# Breakoutboard.net
KiCad netlist of a schematic drawn in Altium Designer
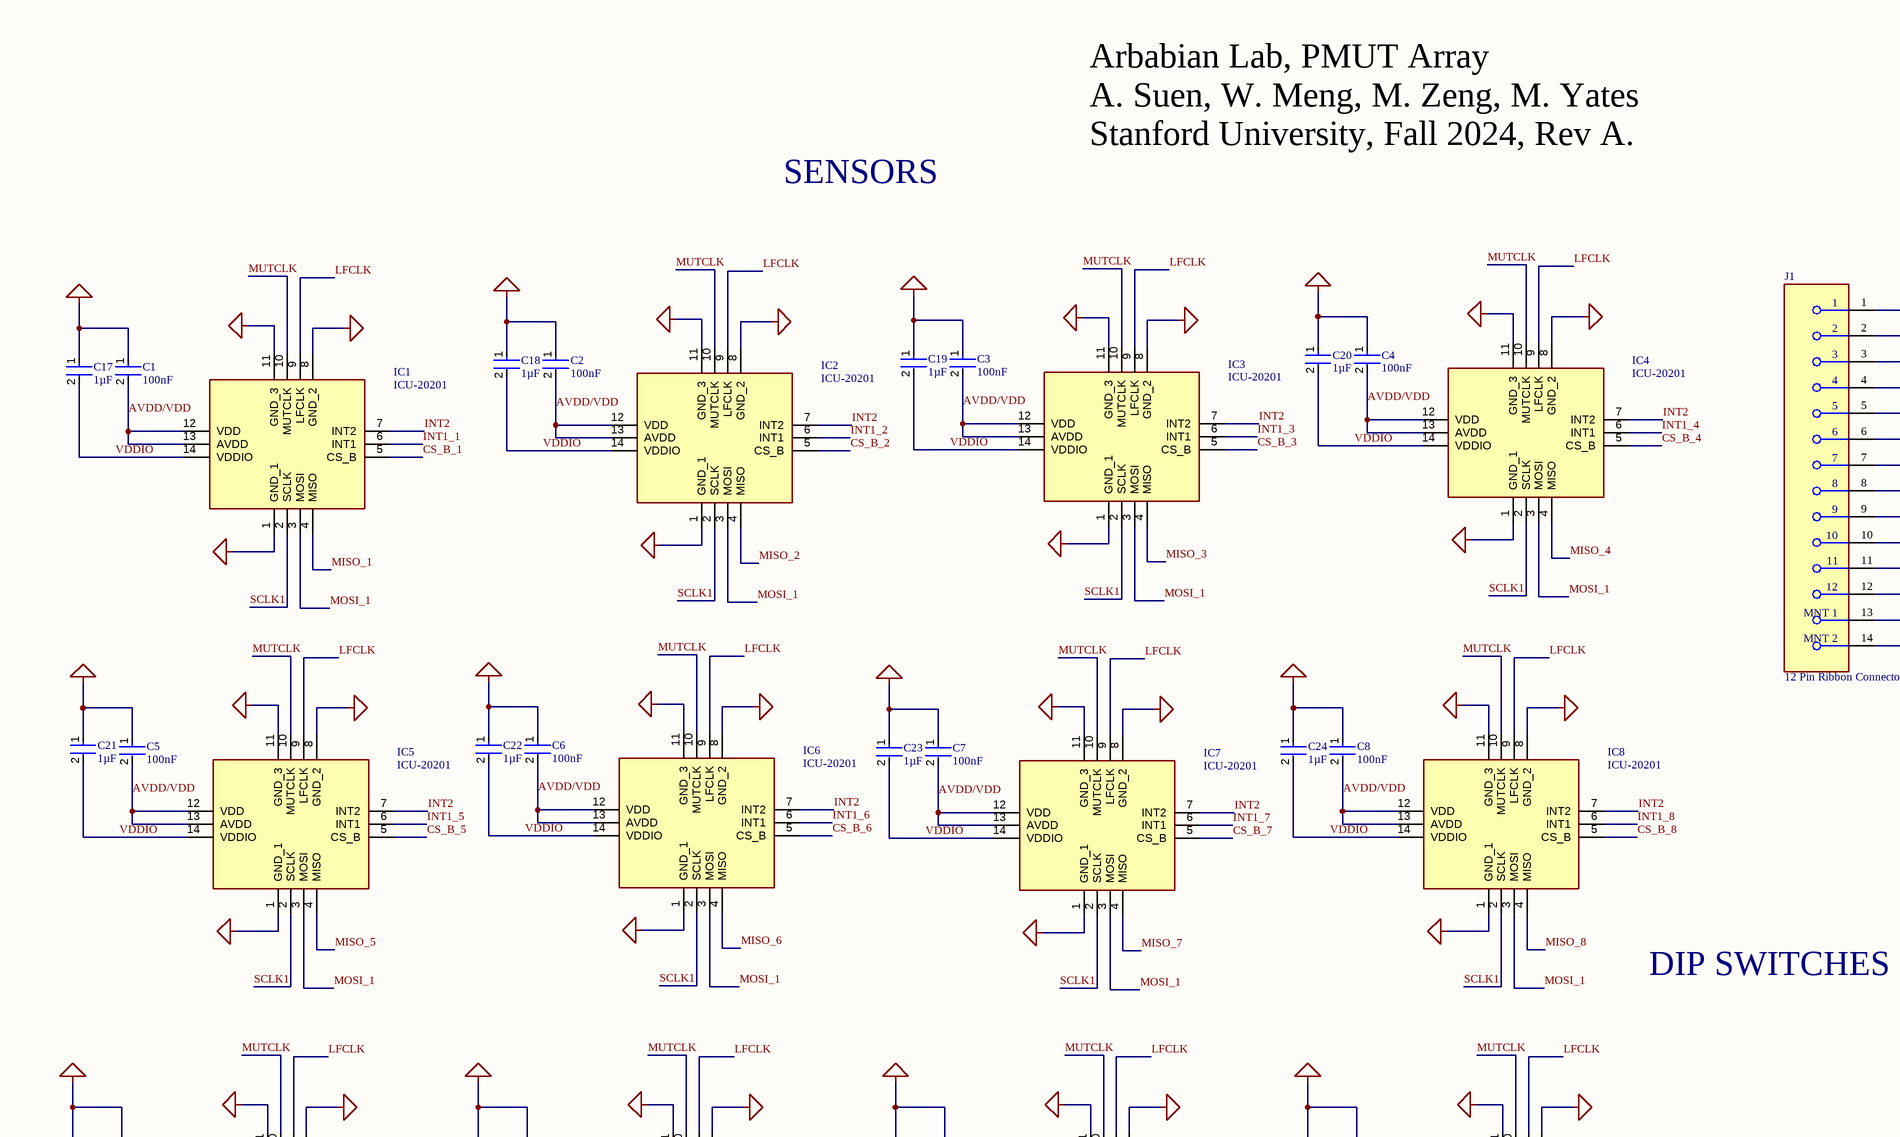
[diagram p0: Breakoutboard.SchDoc, top left]
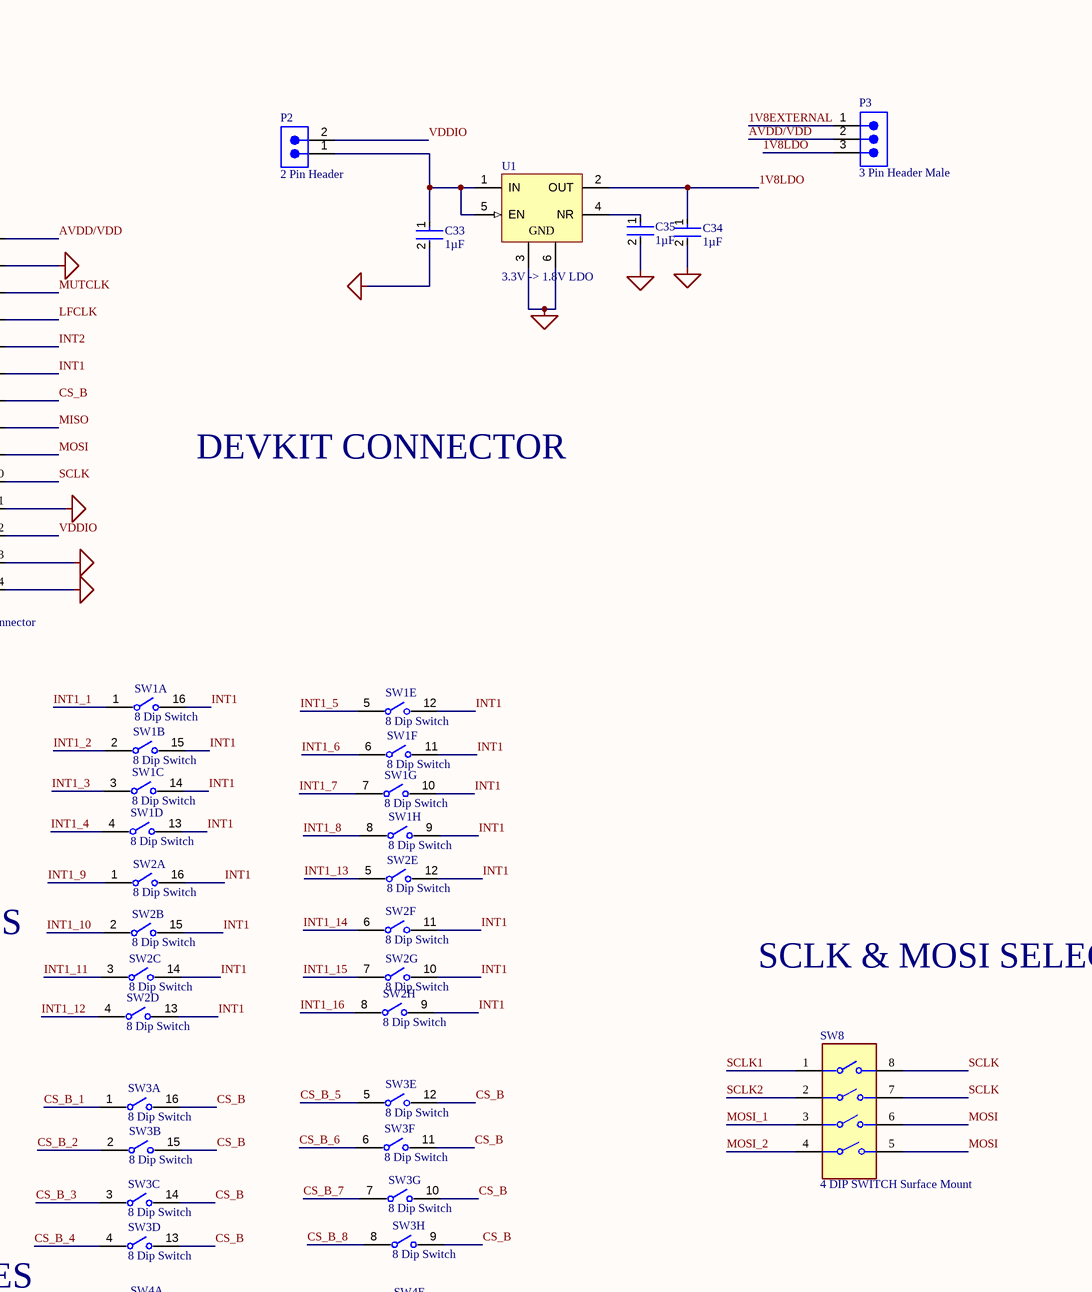
[diagram p1: Breakoutboard.SchDoc, top right]
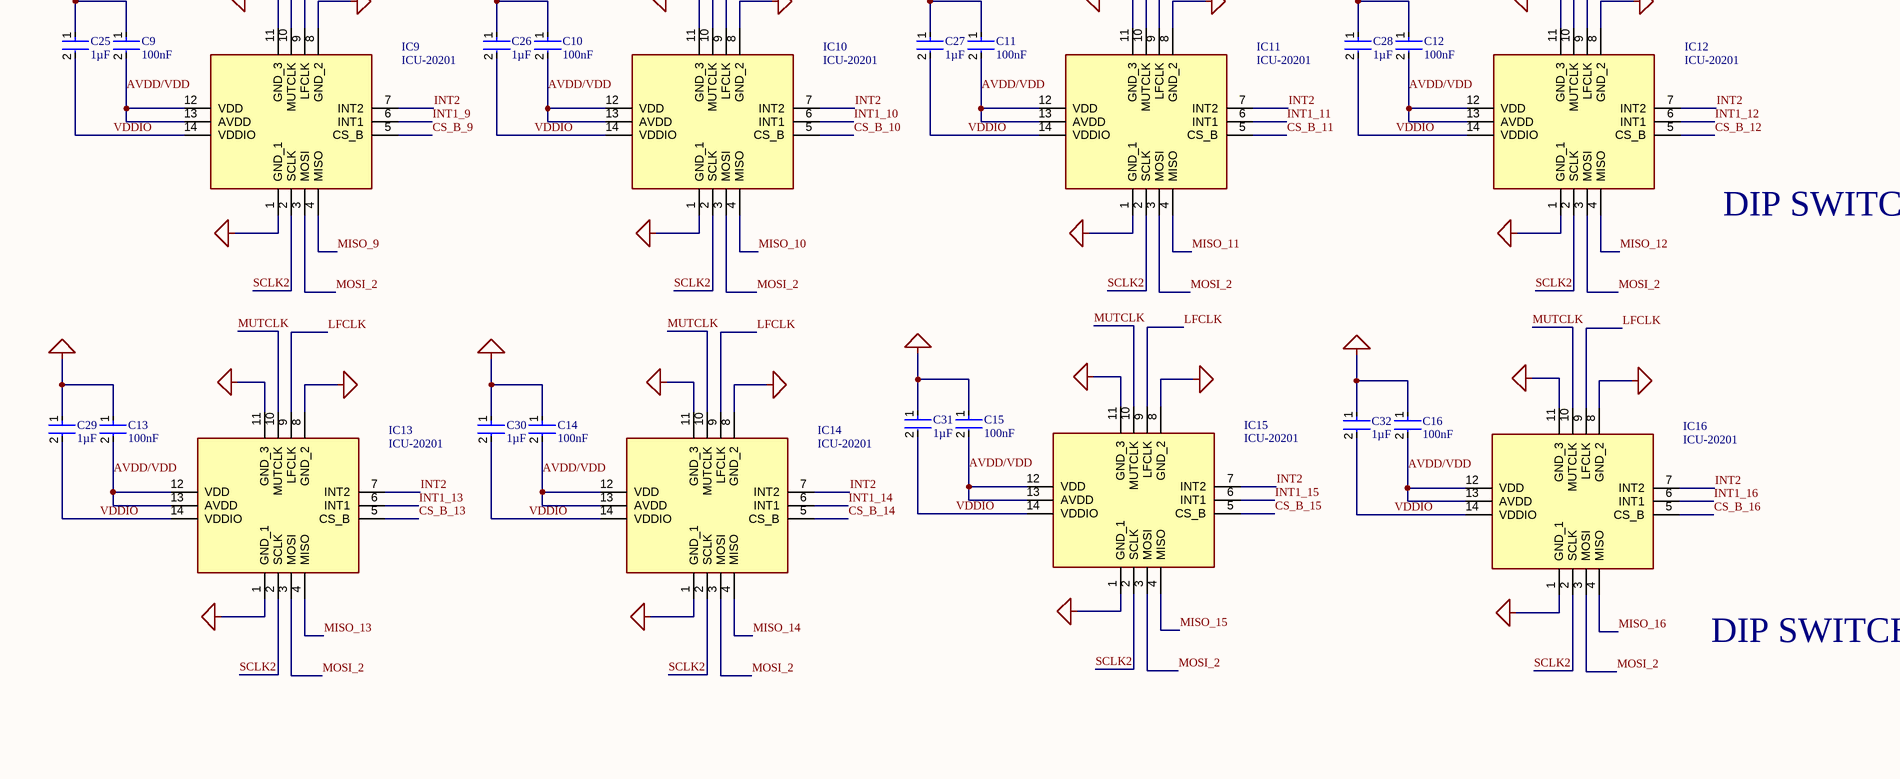
[diagram p2: Breakoutboard.SchDoc, bottom left]
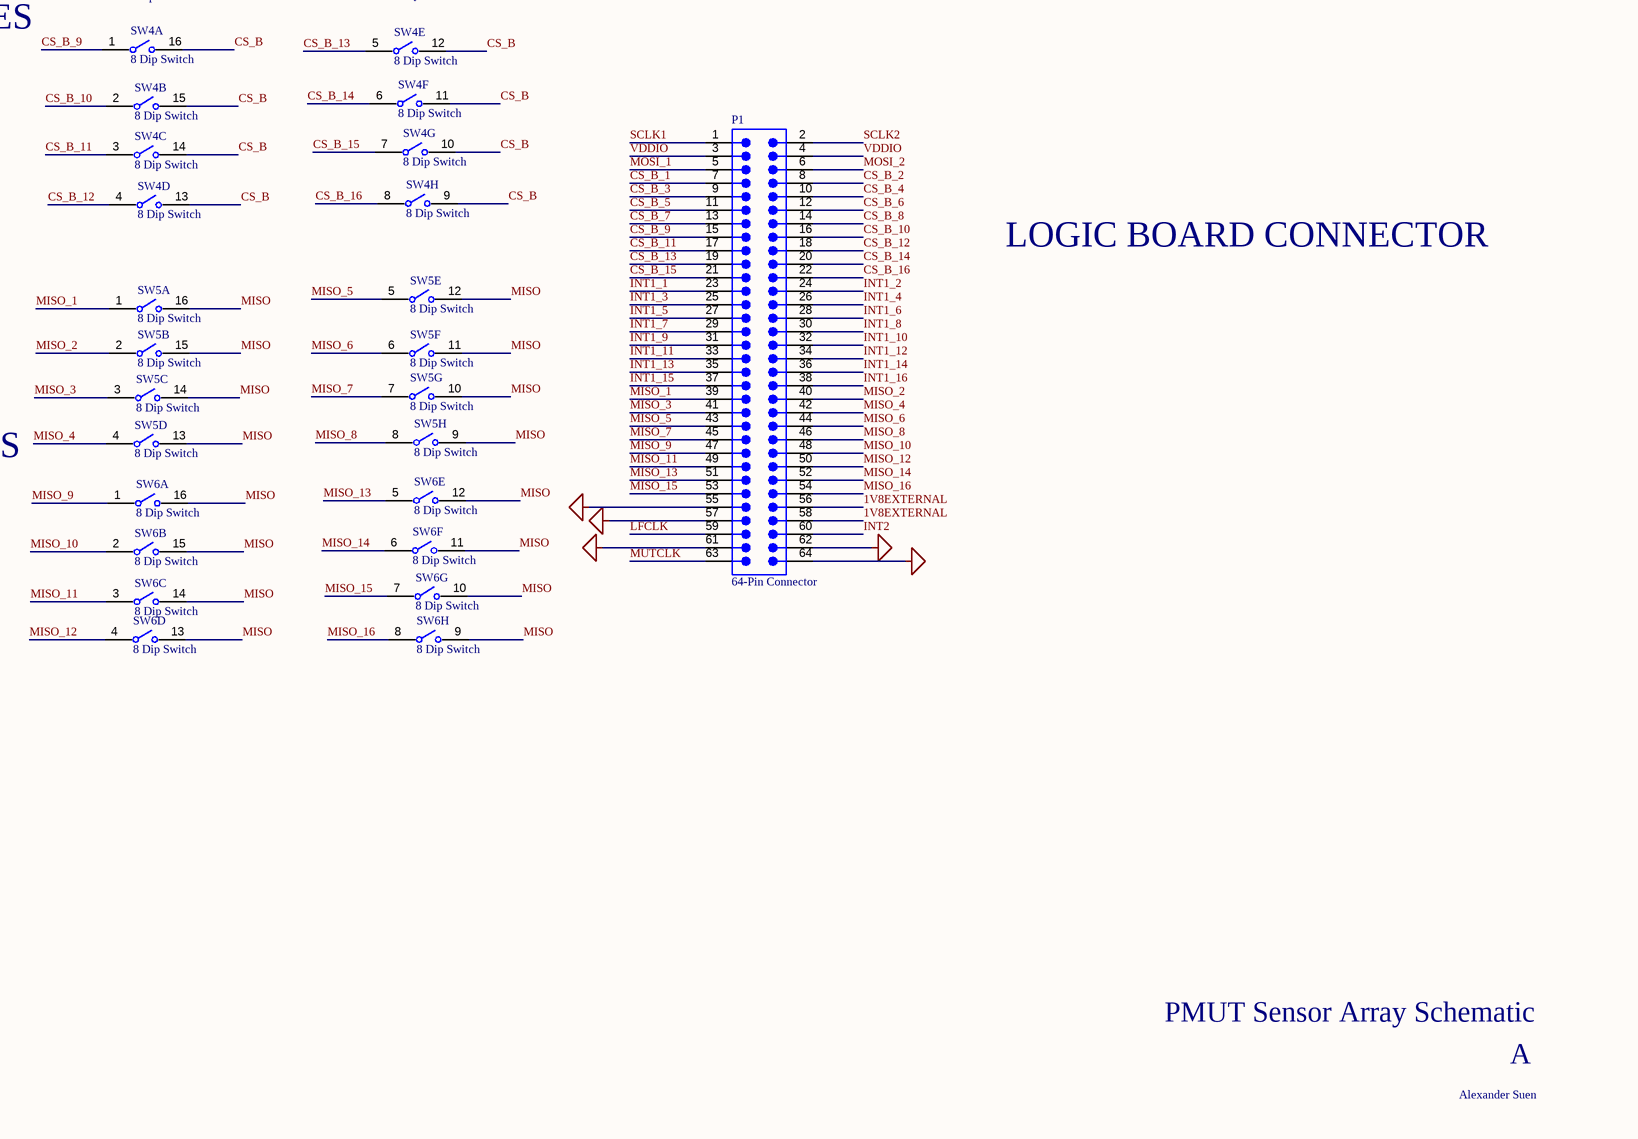
[diagram p3: Breakoutboard.SchDoc, bottom right]

(export (version "E")
  (design (tool "Eeschema 10.0.6"))
  (components
    (comp (ref "C1")
      (value "100nF")
      (footprint "FP-CL17-IPC_B")
      (fields (field (name "Comment") "0.1 uF Capacitator"))
      (libsource (lib "Alexander Suen") (part "b4654b650e69147ec39a6b967a45e02"))
    )
    (comp (ref "C2")
      (value "100nF")
      (footprint "FP-CL17-IPC_B")
      (fields (field (name "Comment") "0.1 uF Capacitator"))
      (libsource (lib "Alexander Suen") (part "b4654b650e69147ec39a6b967a45e02"))
    )
    (comp (ref "C3")
      (value "100nF")
      (footprint "FP-CL17-IPC_B")
      (fields (field (name "Comment") "0.1 uF Capacitator"))
      (libsource (lib "Alexander Suen") (part "b4654b650e69147ec39a6b967a45e02"))
    )
    (comp (ref "C4")
      (value "100nF")
      (footprint "FP-CL17-IPC_B")
      (fields (field (name "Comment") "0.1 uF Capacitator"))
      (libsource (lib "Alexander Suen") (part "b4654b650e69147ec39a6b967a45e02"))
    )
    (comp (ref "C5")
      (value "100nF")
      (footprint "FP-CL17-IPC_B")
      (fields (field (name "Comment") "0.1 uF Capacitator"))
      (libsource (lib "Alexander Suen") (part "b4654b650e69147ec39a6b967a45e02"))
    )
    (comp (ref "C6")
      (value "100nF")
      (footprint "FP-CL17-IPC_B")
      (fields (field (name "Comment") "0.1 uF Capacitator"))
      (libsource (lib "Alexander Suen") (part "b4654b650e69147ec39a6b967a45e02"))
    )
    (comp (ref "C7")
      (value "100nF")
      (footprint "FP-CL17-IPC_B")
      (fields (field (name "Comment") "0.1 uF Capacitator"))
      (libsource (lib "Alexander Suen") (part "b4654b650e69147ec39a6b967a45e02"))
    )
    (comp (ref "C8")
      (value "100nF")
      (footprint "FP-CL17-IPC_B")
      (fields (field (name "Comment") "0.1 uF Capacitator"))
      (libsource (lib "Alexander Suen") (part "b4654b650e69147ec39a6b967a45e02"))
    )
    (comp (ref "C9")
      (value "100nF")
      (footprint "FP-CL17-IPC_B")
      (fields (field (name "Comment") "0.1 uF Capacitator"))
      (libsource (lib "Alexander Suen") (part "b4654b650e69147ec39a6b967a45e02"))
    )
    (comp (ref "C10")
      (value "100nF")
      (footprint "FP-CL17-IPC_B")
      (fields (field (name "Comment") "0.1 uF Capacitator"))
      (libsource (lib "Alexander Suen") (part "b4654b650e69147ec39a6b967a45e02"))
    )
    (comp (ref "C11")
      (value "100nF")
      (footprint "FP-CL17-IPC_B")
      (fields (field (name "Comment") "0.1 uF Capacitator"))
      (libsource (lib "Alexander Suen") (part "b4654b650e69147ec39a6b967a45e02"))
    )
    (comp (ref "C12")
      (value "100nF")
      (footprint "FP-CL17-IPC_B")
      (fields (field (name "Comment") "0.1 uF Capacitator"))
      (libsource (lib "Alexander Suen") (part "b4654b650e69147ec39a6b967a45e02"))
    )
    (comp (ref "C13")
      (value "100nF")
      (footprint "FP-CL17-IPC_B")
      (fields (field (name "Comment") "0.1 uF Capacitator"))
      (libsource (lib "Alexander Suen") (part "b4654b650e69147ec39a6b967a45e02"))
    )
    (comp (ref "C14")
      (value "100nF")
      (footprint "FP-CL17-IPC_B")
      (fields (field (name "Comment") "0.1 uF Capacitator"))
      (libsource (lib "Alexander Suen") (part "b4654b650e69147ec39a6b967a45e02"))
    )
    (comp (ref "C15")
      (value "100nF")
      (footprint "FP-CL17-IPC_B")
      (fields (field (name "Comment") "0.1 uF Capacitator"))
      (libsource (lib "Alexander Suen") (part "b4654b650e69147ec39a6b967a45e02"))
    )
    (comp (ref "C16")
      (value "100nF")
      (footprint "FP-CL17-IPC_B")
      (fields (field (name "Comment") "0.1 uF Capacitator"))
      (libsource (lib "Alexander Suen") (part "b4654b650e69147ec39a6b967a45e02"))
    )
    (comp (ref "C17")
      (value "1µF")
      (footprint "FP-CC0603-DA-IPC_B")
      (fields (field (name "Comment") "1 uF Capacitator"))
      (libsource (lib "Alexander Suen") (part "11868f565c42a9108669ba33697ecf6"))
    )
    (comp (ref "C18")
      (value "1µF")
      (footprint "FP-CC0603-DA-IPC_B")
      (fields (field (name "Comment") "1 uF Capacitator"))
      (libsource (lib "Alexander Suen") (part "11868f565c42a9108669ba33697ecf6"))
    )
    (comp (ref "C19")
      (value "1µF")
      (footprint "FP-CC0603-DA-IPC_B")
      (fields (field (name "Comment") "1 uF Capacitator"))
      (libsource (lib "Alexander Suen") (part "11868f565c42a9108669ba33697ecf6"))
    )
    (comp (ref "C20")
      (value "1µF")
      (footprint "FP-CC0603-DA-IPC_B")
      (fields (field (name "Comment") "1 uF Capacitator"))
      (libsource (lib "Alexander Suen") (part "11868f565c42a9108669ba33697ecf6"))
    )
    (comp (ref "C21")
      (value "1µF")
      (footprint "FP-CC0603-DA-IPC_B")
      (fields (field (name "Comment") "1 uF Capacitator"))
      (libsource (lib "Alexander Suen") (part "11868f565c42a9108669ba33697ecf6"))
    )
    (comp (ref "C22")
      (value "1µF")
      (footprint "FP-CC0603-DA-IPC_B")
      (fields (field (name "Comment") "1 uF Capacitator"))
      (libsource (lib "Alexander Suen") (part "11868f565c42a9108669ba33697ecf6"))
    )
    (comp (ref "C23")
      (value "1µF")
      (footprint "FP-CC0603-DA-IPC_B")
      (fields (field (name "Comment") "1 uF Capacitator"))
      (libsource (lib "Alexander Suen") (part "11868f565c42a9108669ba33697ecf6"))
    )
    (comp (ref "C24")
      (value "1µF")
      (footprint "FP-CC0603-DA-IPC_B")
      (fields (field (name "Comment") "1 uF Capacitator"))
      (libsource (lib "Alexander Suen") (part "11868f565c42a9108669ba33697ecf6"))
    )
    (comp (ref "C25")
      (value "1µF")
      (footprint "FP-CC0603-DA-IPC_B")
      (fields (field (name "Comment") "1 uF Capacitator"))
      (libsource (lib "Alexander Suen") (part "11868f565c42a9108669ba33697ecf6"))
    )
    (comp (ref "C26")
      (value "1µF")
      (footprint "FP-CC0603-DA-IPC_B")
      (fields (field (name "Comment") "1 uF Capacitator"))
      (libsource (lib "Alexander Suen") (part "11868f565c42a9108669ba33697ecf6"))
    )
    (comp (ref "C27")
      (value "1µF")
      (footprint "FP-CC0603-DA-IPC_B")
      (fields (field (name "Comment") "1 uF Capacitator"))
      (libsource (lib "Alexander Suen") (part "11868f565c42a9108669ba33697ecf6"))
    )
    (comp (ref "C28")
      (value "1µF")
      (footprint "FP-CC0603-DA-IPC_B")
      (fields (field (name "Comment") "1 uF Capacitator"))
      (libsource (lib "Alexander Suen") (part "11868f565c42a9108669ba33697ecf6"))
    )
    (comp (ref "C29")
      (value "1µF")
      (footprint "FP-CC0603-DA-IPC_B")
      (fields (field (name "Comment") "1 uF Capacitator"))
      (libsource (lib "Alexander Suen") (part "11868f565c42a9108669ba33697ecf6"))
    )
    (comp (ref "C30")
      (value "1µF")
      (footprint "FP-CC0603-DA-IPC_B")
      (fields (field (name "Comment") "1 uF Capacitator"))
      (libsource (lib "Alexander Suen") (part "11868f565c42a9108669ba33697ecf6"))
    )
    (comp (ref "C31")
      (value "1µF")
      (footprint "FP-CC0603-DA-IPC_B")
      (fields (field (name "Comment") "1 uF Capacitator"))
      (libsource (lib "Alexander Suen") (part "11868f565c42a9108669ba33697ecf6"))
    )
    (comp (ref "C32")
      (value "1µF")
      (footprint "FP-CC0603-DA-IPC_B")
      (fields (field (name "Comment") "1 uF Capacitator"))
      (libsource (lib "Alexander Suen") (part "11868f565c42a9108669ba33697ecf6"))
    )
    (comp (ref "C33")
      (value "1µF")
      (footprint "FP-CC0603-DA-IPC_B")
      (fields (field (name "Comment") "1 uF Capacitator"))
      (libsource (lib "Alexander Suen") (part "11868f565c42a9108669ba33697ecf6"))
    )
    (comp (ref "C34")
      (value "1µF")
      (footprint "FP-CC0603-DA-IPC_B")
      (fields (field (name "Comment") "1 uF Capacitator"))
      (libsource (lib "Alexander Suen") (part "11868f565c42a9108669ba33697ecf6"))
    )
    (comp (ref "C35")
      (value "1µF")
      (footprint "FP-CC0603-DA-IPC_B")
      (fields (field (name "Comment") "1 uF Capacitator"))
      (libsource (lib "Alexander Suen") (part "11868f565c42a9108669ba33697ecf6"))
    )
    (comp (ref "IC1")
      (value "ICU-20201")
      (footprint "ICU20201")
      (description "Integrated Circuit")
      (fields (field (name "MOUSER PART NUMBER") "410-ICU-20201"))
      (libsource (lib "*") (part "ICU-20201"))
    )
    (comp (ref "IC2")
      (value "ICU-20201")
      (footprint "ICU20201")
      (description "Integrated Circuit")
      (fields (field (name "MOUSER PART NUMBER") "410-ICU-20201"))
      (libsource (lib "*") (part "ICU-20201"))
    )
    (comp (ref "IC3")
      (value "ICU-20201")
      (footprint "ICU20201")
      (description "Integrated Circuit")
      (fields (field (name "MOUSER PART NUMBER") "410-ICU-20201"))
      (libsource (lib "*") (part "ICU-20201"))
    )
    (comp (ref "IC4")
      (value "ICU-20201")
      (footprint "ICU20201")
      (description "Integrated Circuit")
      (fields (field (name "MOUSER PART NUMBER") "410-ICU-20201"))
      (libsource (lib "*") (part "ICU-20201"))
    )
    (comp (ref "IC5")
      (value "ICU-20201")
      (footprint "ICU20201")
      (description "Integrated Circuit")
      (fields (field (name "MOUSER PART NUMBER") "410-ICU-20201"))
      (libsource (lib "*") (part "ICU-20201"))
    )
    (comp (ref "IC6")
      (value "ICU-20201")
      (footprint "ICU20201")
      (description "Integrated Circuit")
      (fields (field (name "MOUSER PART NUMBER") "410-ICU-20201"))
      (libsource (lib "*") (part "ICU-20201"))
    )
    (comp (ref "IC7")
      (value "ICU-20201")
      (footprint "ICU20201")
      (description "Integrated Circuit")
      (fields (field (name "MOUSER PART NUMBER") "410-ICU-20201"))
      (libsource (lib "*") (part "ICU-20201"))
    )
    (comp (ref "IC8")
      (value "ICU-20201")
      (footprint "ICU20201")
      (description "Integrated Circuit")
      (fields (field (name "MOUSER PART NUMBER") "410-ICU-20201"))
      (libsource (lib "*") (part "ICU-20201"))
    )
    (comp (ref "IC9")
      (value "ICU-20201")
      (footprint "ICU20201")
      (description "Integrated Circuit")
      (fields (field (name "MOUSER PART NUMBER") "410-ICU-20201"))
      (libsource (lib "*") (part "ICU-20201"))
    )
    (comp (ref "IC10")
      (value "ICU-20201")
      (footprint "ICU20201")
      (description "Integrated Circuit")
      (fields (field (name "MOUSER PART NUMBER") "410-ICU-20201"))
      (libsource (lib "*") (part "ICU-20201"))
    )
    (comp (ref "IC11")
      (value "ICU-20201")
      (footprint "ICU20201")
      (description "Integrated Circuit")
      (fields (field (name "MOUSER PART NUMBER") "410-ICU-20201"))
      (libsource (lib "*") (part "ICU-20201"))
    )
    (comp (ref "IC12")
      (value "ICU-20201")
      (footprint "ICU20201")
      (description "Integrated Circuit")
      (fields (field (name "MOUSER PART NUMBER") "410-ICU-20201"))
      (libsource (lib "*") (part "ICU-20201"))
    )
    (comp (ref "IC13")
      (value "ICU-20201")
      (footprint "ICU20201")
      (description "Integrated Circuit")
      (fields (field (name "MOUSER PART NUMBER") "410-ICU-20201"))
      (libsource (lib "*") (part "ICU-20201"))
    )
    (comp (ref "IC14")
      (value "ICU-20201")
      (footprint "ICU20201")
      (description "Integrated Circuit")
      (fields (field (name "MOUSER PART NUMBER") "410-ICU-20201"))
      (libsource (lib "*") (part "ICU-20201"))
    )
    (comp (ref "IC15")
      (value "ICU-20201")
      (footprint "ICU20201")
      (description "Integrated Circuit")
      (fields (field (name "MOUSER PART NUMBER") "410-ICU-20201"))
      (libsource (lib "*") (part "ICU-20201"))
    )
    (comp (ref "IC16")
      (value "ICU-20201")
      (footprint "ICU20201")
      (description "Integrated Circuit")
      (fields (field (name "MOUSER PART NUMBER") "410-ICU-20201"))
      (libsource (lib "*") (part "ICU-20201"))
    )
    (comp (ref "J1")
      (value "12 Pin Ribbon Connector")
      (footprint "FP-505110-1292-MFG")
      (description "Conn FFC/FPC Connector SKT 12 POS 0.5mm Solder RA SMD Easy-On™ T/R")
      (libsource (lib "Alexander Suen") (part "4817814962c85e6ab358b5832e8ced4"))
    )
    (comp (ref "P1")
      (value "64-Pin Connector")
      (footprint "61306421021")
      (libsource (lib "Alexander Suen") (part "Header_Male_2R_64P"))
    )
    (comp (ref "P2")
      (value "2 Pin Header")
      (footprint "61300211121")
      (libsource (lib "Alexander Suen") (part "Header_Male_1R_02P"))
    )
    (comp (ref "P3")
      (value "3 Pin Header Male")
      (footprint "61300311121")
      (libsource (lib "Alexander Suen") (part "Header_Male_1R_03P"))
    )
    (comp (ref "SW1")
      (value "8 Dip Switch")
      (footprint "FP-1-1571983-1-MFG")
      (libsource (lib "Alexander Suen") (part "970e54b12a704161c1b4a03f85903bf"))
    )
    (comp (ref "SW2")
      (value "8 Dip Switch")
      (footprint "FP-1-1571983-1-MFG")
      (libsource (lib "Alexander Suen") (part "970e54b12a704161c1b4a03f85903bf"))
    )
    (comp (ref "SW3")
      (value "8 Dip Switch")
      (footprint "FP-1-1571983-1-MFG")
      (libsource (lib "Alexander Suen") (part "970e54b12a704161c1b4a03f85903bf"))
    )
    (comp (ref "SW4")
      (value "8 Dip Switch")
      (footprint "FP-1-1571983-1-MFG")
      (libsource (lib "Alexander Suen") (part "970e54b12a704161c1b4a03f85903bf"))
    )
    (comp (ref "SW5")
      (value "8 Dip Switch")
      (footprint "FP-1-1571983-1-MFG")
      (libsource (lib "Alexander Suen") (part "970e54b12a704161c1b4a03f85903bf"))
    )
    (comp (ref "SW6")
      (value "8 Dip Switch")
      (footprint "FP-1-1571983-1-MFG")
      (libsource (lib "Alexander Suen") (part "970e54b12a704161c1b4a03f85903bf"))
    )
    (comp (ref "SW8")
      (value "4 DIP SWITCH Surface Mount")
      (footprint "FP-218-4LPSTR-MFG")
      (libsource (lib "Alexander Suen") (part "a78650ae27aee94b64e9c93150c7d5d"))
    )
    (comp (ref "U1")
      (value "3.3V -> 1.8V LDO")
      (footprint "DCQ0006A_N")
      (description "Fixed Positive LDO Regulator, 1.8V, 0.5V Dropout, BICMOS, PDSO6")
      (libsource (lib "Alexander Suen") (part "TI-TPS73XXXDCQ6"))
    )
  )
  (nets
    (net (code "1") (name "/1V8EXTERNAL") (class "Default")
      (node (ref "P1") (pin "56") (pinfunction "56_56") (pintype "passive"))
      (node (ref "P1") (pin "58") (pinfunction "58_58") (pintype "passive"))
      (node (ref "P3") (pin "1") (pinfunction "1_1") (pintype "passive"))
    )
    (net (code "2") (name "/1V8LDO") (class "Default")
      (node (ref "C34") (pin "1") (pinfunction "1_1") (pintype "passive"))
      (node (ref "P3") (pin "3") (pinfunction "3_3") (pintype "passive"))
      (node (ref "U1") (pin "2") (pinfunction "OUT_2") (pintype "power_in"))
    )
    (net (code "3") (name "/AVDD{slash}VDD") (class "Default")
      (node (ref "C1") (pin "2") (pinfunction "2_2") (pintype "passive"))
      (node (ref "C10") (pin "2") (pinfunction "2_2") (pintype "passive"))
      (node (ref "C11") (pin "2") (pinfunction "2_2") (pintype "passive"))
      (node (ref "C12") (pin "2") (pinfunction "2_2") (pintype "passive"))
      (node (ref "C13") (pin "2") (pinfunction "2_2") (pintype "passive"))
      (node (ref "C14") (pin "2") (pinfunction "2_2") (pintype "passive"))
      (node (ref "C15") (pin "2") (pinfunction "2_2") (pintype "passive"))
      (node (ref "C16") (pin "2") (pinfunction "2_2") (pintype "passive"))
      (node (ref "C2") (pin "2") (pinfunction "2_2") (pintype "passive"))
      (node (ref "C3") (pin "2") (pinfunction "2_2") (pintype "passive"))
      (node (ref "C4") (pin "2") (pinfunction "2_2") (pintype "passive"))
      (node (ref "C5") (pin "2") (pinfunction "2_2") (pintype "passive"))
      (node (ref "C6") (pin "2") (pinfunction "2_2") (pintype "passive"))
      (node (ref "C7") (pin "2") (pinfunction "2_2") (pintype "passive"))
      (node (ref "C8") (pin "2") (pinfunction "2_2") (pintype "passive"))
      (node (ref "C9") (pin "2") (pinfunction "2_2") (pintype "passive"))
      (node (ref "IC1") (pin "12") (pinfunction "VDD_12") (pintype "passive"))
      (node (ref "IC1") (pin "13") (pinfunction "AVDD_13") (pintype "passive"))
      (node (ref "IC10") (pin "12") (pinfunction "VDD_12") (pintype "passive"))
      (node (ref "IC10") (pin "13") (pinfunction "AVDD_13") (pintype "passive"))
      (node (ref "IC11") (pin "12") (pinfunction "VDD_12") (pintype "passive"))
      (node (ref "IC11") (pin "13") (pinfunction "AVDD_13") (pintype "passive"))
      (node (ref "IC12") (pin "12") (pinfunction "VDD_12") (pintype "passive"))
      (node (ref "IC12") (pin "13") (pinfunction "AVDD_13") (pintype "passive"))
      (node (ref "IC13") (pin "12") (pinfunction "VDD_12") (pintype "passive"))
      (node (ref "IC13") (pin "13") (pinfunction "AVDD_13") (pintype "passive"))
      (node (ref "IC14") (pin "12") (pinfunction "VDD_12") (pintype "passive"))
      (node (ref "IC14") (pin "13") (pinfunction "AVDD_13") (pintype "passive"))
      (node (ref "IC15") (pin "12") (pinfunction "VDD_12") (pintype "passive"))
      (node (ref "IC15") (pin "13") (pinfunction "AVDD_13") (pintype "passive"))
      (node (ref "IC16") (pin "12") (pinfunction "VDD_12") (pintype "passive"))
      (node (ref "IC16") (pin "13") (pinfunction "AVDD_13") (pintype "passive"))
      (node (ref "IC2") (pin "12") (pinfunction "VDD_12") (pintype "passive"))
      (node (ref "IC2") (pin "13") (pinfunction "AVDD_13") (pintype "passive"))
      (node (ref "IC3") (pin "12") (pinfunction "VDD_12") (pintype "passive"))
      (node (ref "IC3") (pin "13") (pinfunction "AVDD_13") (pintype "passive"))
      (node (ref "IC4") (pin "12") (pinfunction "VDD_12") (pintype "passive"))
      (node (ref "IC4") (pin "13") (pinfunction "AVDD_13") (pintype "passive"))
      (node (ref "IC5") (pin "12") (pinfunction "VDD_12") (pintype "passive"))
      (node (ref "IC5") (pin "13") (pinfunction "AVDD_13") (pintype "passive"))
      (node (ref "IC6") (pin "12") (pinfunction "VDD_12") (pintype "passive"))
      (node (ref "IC6") (pin "13") (pinfunction "AVDD_13") (pintype "passive"))
      (node (ref "IC7") (pin "12") (pinfunction "VDD_12") (pintype "passive"))
      (node (ref "IC7") (pin "13") (pinfunction "AVDD_13") (pintype "passive"))
      (node (ref "IC8") (pin "12") (pinfunction "VDD_12") (pintype "passive"))
      (node (ref "IC8") (pin "13") (pinfunction "AVDD_13") (pintype "passive"))
      (node (ref "IC9") (pin "12") (pinfunction "VDD_12") (pintype "passive"))
      (node (ref "IC9") (pin "13") (pinfunction "AVDD_13") (pintype "passive"))
      (node (ref "J1") (pin "1") (pinfunction "1_1") (pintype "passive"))
      (node (ref "P3") (pin "2") (pinfunction "2_2") (pintype "passive"))
    )
    (net (code "4") (name "/CS_B") (class "Default")
      (node (ref "J1") (pin "7") (pinfunction "7_7") (pintype "passive"))
      (node (ref "SW3") (pin "10") (pinfunction "10_10") (pintype "passive"))
      (node (ref "SW3") (pin "11") (pinfunction "11_11") (pintype "passive"))
      (node (ref "SW3") (pin "12") (pinfunction "12_12") (pintype "passive"))
      (node (ref "SW3") (pin "13") (pinfunction "13_13") (pintype "passive"))
      (node (ref "SW3") (pin "14") (pinfunction "14_14") (pintype "passive"))
      (node (ref "SW3") (pin "15") (pinfunction "15_15") (pintype "passive"))
      (node (ref "SW3") (pin "16") (pinfunction "16_16") (pintype "passive"))
      (node (ref "SW3") (pin "9") (pinfunction "9_9") (pintype "passive"))
      (node (ref "SW4") (pin "10") (pinfunction "10_10") (pintype "passive"))
      (node (ref "SW4") (pin "11") (pinfunction "11_11") (pintype "passive"))
      (node (ref "SW4") (pin "12") (pinfunction "12_12") (pintype "passive"))
      (node (ref "SW4") (pin "13") (pinfunction "13_13") (pintype "passive"))
      (node (ref "SW4") (pin "14") (pinfunction "14_14") (pintype "passive"))
      (node (ref "SW4") (pin "15") (pinfunction "15_15") (pintype "passive"))
      (node (ref "SW4") (pin "16") (pinfunction "16_16") (pintype "passive"))
      (node (ref "SW4") (pin "9") (pinfunction "9_9") (pintype "passive"))
    )
    (net (code "5") (name "/CS_B_1") (class "Default")
      (node (ref "IC1") (pin "5") (pinfunction "CS_B_5") (pintype "passive"))
      (node (ref "P1") (pin "7") (pinfunction "7_7") (pintype "passive"))
      (node (ref "SW3") (pin "1") (pinfunction "1_1") (pintype "passive"))
    )
    (net (code "6") (name "/CS_B_2") (class "Default")
      (node (ref "IC2") (pin "5") (pinfunction "CS_B_5") (pintype "passive"))
      (node (ref "P1") (pin "8") (pinfunction "8_8") (pintype "passive"))
      (node (ref "SW3") (pin "2") (pinfunction "2_2") (pintype "passive"))
    )
    (net (code "7") (name "/CS_B_3") (class "Default")
      (node (ref "IC3") (pin "5") (pinfunction "CS_B_5") (pintype "passive"))
      (node (ref "P1") (pin "9") (pinfunction "9_9") (pintype "passive"))
      (node (ref "SW3") (pin "3") (pinfunction "3_3") (pintype "passive"))
    )
    (net (code "8") (name "/CS_B_4") (class "Default")
      (node (ref "IC4") (pin "5") (pinfunction "CS_B_5") (pintype "passive"))
      (node (ref "P1") (pin "10") (pinfunction "10_10") (pintype "passive"))
      (node (ref "SW3") (pin "4") (pinfunction "4_4") (pintype "passive"))
    )
    (net (code "9") (name "/CS_B_5") (class "Default")
      (node (ref "IC5") (pin "5") (pinfunction "CS_B_5") (pintype "passive"))
      (node (ref "P1") (pin "11") (pinfunction "11_11") (pintype "passive"))
      (node (ref "SW3") (pin "5") (pinfunction "5_5") (pintype "passive"))
    )
    (net (code "10") (name "/CS_B_6") (class "Default")
      (node (ref "IC6") (pin "5") (pinfunction "CS_B_5") (pintype "passive"))
      (node (ref "P1") (pin "12") (pinfunction "12_12") (pintype "passive"))
      (node (ref "SW3") (pin "6") (pinfunction "6_6") (pintype "passive"))
    )
    (net (code "11") (name "/CS_B_7") (class "Default")
      (node (ref "IC7") (pin "5") (pinfunction "CS_B_5") (pintype "passive"))
      (node (ref "P1") (pin "13") (pinfunction "13_13") (pintype "passive"))
      (node (ref "SW3") (pin "7") (pinfunction "7_7") (pintype "passive"))
    )
    (net (code "12") (name "/CS_B_8") (class "Default")
      (node (ref "IC8") (pin "5") (pinfunction "CS_B_5") (pintype "passive"))
      (node (ref "P1") (pin "14") (pinfunction "14_14") (pintype "passive"))
      (node (ref "SW3") (pin "8") (pinfunction "8_8") (pintype "passive"))
    )
    (net (code "13") (name "/CS_B_9") (class "Default")
      (node (ref "IC9") (pin "5") (pinfunction "CS_B_5") (pintype "passive"))
      (node (ref "P1") (pin "15") (pinfunction "15_15") (pintype "passive"))
      (node (ref "SW4") (pin "1") (pinfunction "1_1") (pintype "passive"))
    )
    (net (code "14") (name "/CS_B_10") (class "Default")
      (node (ref "IC10") (pin "5") (pinfunction "CS_B_5") (pintype "passive"))
      (node (ref "P1") (pin "16") (pinfunction "16_16") (pintype "passive"))
      (node (ref "SW4") (pin "2") (pinfunction "2_2") (pintype "passive"))
    )
    (net (code "15") (name "/CS_B_11") (class "Default")
      (node (ref "IC11") (pin "5") (pinfunction "CS_B_5") (pintype "passive"))
      (node (ref "P1") (pin "17") (pinfunction "17_17") (pintype "passive"))
      (node (ref "SW4") (pin "3") (pinfunction "3_3") (pintype "passive"))
    )
    (net (code "16") (name "/CS_B_12") (class "Default")
      (node (ref "IC12") (pin "5") (pinfunction "CS_B_5") (pintype "passive"))
      (node (ref "P1") (pin "18") (pinfunction "18_18") (pintype "passive"))
      (node (ref "SW4") (pin "4") (pinfunction "4_4") (pintype "passive"))
    )
    (net (code "17") (name "/CS_B_13") (class "Default")
      (node (ref "IC13") (pin "5") (pinfunction "CS_B_5") (pintype "passive"))
      (node (ref "P1") (pin "19") (pinfunction "19_19") (pintype "passive"))
      (node (ref "SW4") (pin "5") (pinfunction "5_5") (pintype "passive"))
    )
    (net (code "18") (name "/CS_B_14") (class "Default")
      (node (ref "IC14") (pin "5") (pinfunction "CS_B_5") (pintype "passive"))
      (node (ref "P1") (pin "20") (pinfunction "20_20") (pintype "passive"))
      (node (ref "SW4") (pin "6") (pinfunction "6_6") (pintype "passive"))
    )
    (net (code "19") (name "/CS_B_15") (class "Default")
      (node (ref "IC15") (pin "5") (pinfunction "CS_B_5") (pintype "passive"))
      (node (ref "P1") (pin "21") (pinfunction "21_21") (pintype "passive"))
      (node (ref "SW4") (pin "7") (pinfunction "7_7") (pintype "passive"))
    )
    (net (code "20") (name "/CS_B_16") (class "Default")
      (node (ref "IC16") (pin "5") (pinfunction "CS_B_5") (pintype "passive"))
      (node (ref "P1") (pin "22") (pinfunction "22_22") (pintype "passive"))
      (node (ref "SW4") (pin "8") (pinfunction "8_8") (pintype "passive"))
    )
    (net (code "21") (name "/INT1") (class "Default")
      (node (ref "J1") (pin "6") (pinfunction "6_6") (pintype "passive"))
      (node (ref "SW1") (pin "10") (pinfunction "10_10") (pintype "passive"))
      (node (ref "SW1") (pin "11") (pinfunction "11_11") (pintype "passive"))
      (node (ref "SW1") (pin "12") (pinfunction "12_12") (pintype "passive"))
      (node (ref "SW1") (pin "13") (pinfunction "13_13") (pintype "passive"))
      (node (ref "SW1") (pin "14") (pinfunction "14_14") (pintype "passive"))
      (node (ref "SW1") (pin "15") (pinfunction "15_15") (pintype "passive"))
      (node (ref "SW1") (pin "16") (pinfunction "16_16") (pintype "passive"))
      (node (ref "SW1") (pin "9") (pinfunction "9_9") (pintype "passive"))
      (node (ref "SW2") (pin "10") (pinfunction "10_10") (pintype "passive"))
      (node (ref "SW2") (pin "11") (pinfunction "11_11") (pintype "passive"))
      (node (ref "SW2") (pin "12") (pinfunction "12_12") (pintype "passive"))
      (node (ref "SW2") (pin "13") (pinfunction "13_13") (pintype "passive"))
      (node (ref "SW2") (pin "14") (pinfunction "14_14") (pintype "passive"))
      (node (ref "SW2") (pin "15") (pinfunction "15_15") (pintype "passive"))
      (node (ref "SW2") (pin "16") (pinfunction "16_16") (pintype "passive"))
      (node (ref "SW2") (pin "9") (pinfunction "9_9") (pintype "passive"))
    )
    (net (code "22") (name "/INT1_1") (class "Default")
      (node (ref "IC1") (pin "6") (pinfunction "INT1_6") (pintype "passive"))
      (node (ref "P1") (pin "23") (pinfunction "23_23") (pintype "passive"))
      (node (ref "SW1") (pin "1") (pinfunction "1_1") (pintype "passive"))
    )
    (net (code "23") (name "/INT1_2") (class "Default")
      (node (ref "IC2") (pin "6") (pinfunction "INT1_6") (pintype "passive"))
      (node (ref "P1") (pin "24") (pinfunction "24_24") (pintype "passive"))
      (node (ref "SW1") (pin "2") (pinfunction "2_2") (pintype "passive"))
    )
    (net (code "24") (name "/INT1_3") (class "Default")
      (node (ref "IC3") (pin "6") (pinfunction "INT1_6") (pintype "passive"))
      (node (ref "P1") (pin "25") (pinfunction "25_25") (pintype "passive"))
      (node (ref "SW1") (pin "3") (pinfunction "3_3") (pintype "passive"))
    )
    (net (code "25") (name "/INT1_4") (class "Default")
      (node (ref "IC4") (pin "6") (pinfunction "INT1_6") (pintype "passive"))
      (node (ref "P1") (pin "26") (pinfunction "26_26") (pintype "passive"))
      (node (ref "SW1") (pin "4") (pinfunction "4_4") (pintype "passive"))
    )
    (net (code "26") (name "/INT1_5") (class "Default")
      (node (ref "IC5") (pin "6") (pinfunction "INT1_6") (pintype "passive"))
      (node (ref "P1") (pin "27") (pinfunction "27_27") (pintype "passive"))
      (node (ref "SW1") (pin "5") (pinfunction "5_5") (pintype "passive"))
    )
    (net (code "27") (name "/INT1_6") (class "Default")
      (node (ref "IC6") (pin "6") (pinfunction "INT1_6") (pintype "passive"))
      (node (ref "P1") (pin "28") (pinfunction "28_28") (pintype "passive"))
      (node (ref "SW1") (pin "6") (pinfunction "6_6") (pintype "passive"))
    )
    (net (code "28") (name "/INT1_7") (class "Default")
      (node (ref "IC7") (pin "6") (pinfunction "INT1_6") (pintype "passive"))
      (node (ref "P1") (pin "29") (pinfunction "29_29") (pintype "passive"))
      (node (ref "SW1") (pin "7") (pinfunction "7_7") (pintype "passive"))
    )
    (net (code "29") (name "/INT1_8") (class "Default")
      (node (ref "IC8") (pin "6") (pinfunction "INT1_6") (pintype "passive"))
      (node (ref "P1") (pin "30") (pinfunction "30_30") (pintype "passive"))
      (node (ref "SW1") (pin "8") (pinfunction "8_8") (pintype "passive"))
    )
    (net (code "30") (name "/INT1_9") (class "Default")
      (node (ref "IC9") (pin "6") (pinfunction "INT1_6") (pintype "passive"))
      (node (ref "P1") (pin "31") (pinfunction "31_31") (pintype "passive"))
      (node (ref "SW2") (pin "1") (pinfunction "1_1") (pintype "passive"))
    )
    (net (code "31") (name "/INT1_10") (class "Default")
      (node (ref "IC10") (pin "6") (pinfunction "INT1_6") (pintype "passive"))
      (node (ref "P1") (pin "32") (pinfunction "32_32") (pintype "passive"))
      (node (ref "SW2") (pin "2") (pinfunction "2_2") (pintype "passive"))
    )
    (net (code "32") (name "/INT1_11") (class "Default")
      (node (ref "IC11") (pin "6") (pinfunction "INT1_6") (pintype "passive"))
      (node (ref "P1") (pin "33") (pinfunction "33_33") (pintype "passive"))
      (node (ref "SW2") (pin "3") (pinfunction "3_3") (pintype "passive"))
    )
    (net (code "33") (name "/INT1_12") (class "Default")
      (node (ref "IC12") (pin "6") (pinfunction "INT1_6") (pintype "passive"))
      (node (ref "P1") (pin "34") (pinfunction "34_34") (pintype "passive"))
      (node (ref "SW2") (pin "4") (pinfunction "4_4") (pintype "passive"))
    )
    (net (code "34") (name "/INT1_13") (class "Default")
      (node (ref "IC13") (pin "6") (pinfunction "INT1_6") (pintype "passive"))
      (node (ref "P1") (pin "35") (pinfunction "35_35") (pintype "passive"))
      (node (ref "SW2") (pin "5") (pinfunction "5_5") (pintype "passive"))
    )
    (net (code "35") (name "/INT1_14") (class "Default")
      (node (ref "IC14") (pin "6") (pinfunction "INT1_6") (pintype "passive"))
      (node (ref "P1") (pin "36") (pinfunction "36_36") (pintype "passive"))
      (node (ref "SW2") (pin "6") (pinfunction "6_6") (pintype "passive"))
    )
    (net (code "36") (name "/INT1_15") (class "Default")
      (node (ref "IC15") (pin "6") (pinfunction "INT1_6") (pintype "passive"))
      (node (ref "P1") (pin "37") (pinfunction "37_37") (pintype "passive"))
      (node (ref "SW2") (pin "7") (pinfunction "7_7") (pintype "passive"))
    )
    (net (code "37") (name "/INT1_16") (class "Default")
      (node (ref "IC16") (pin "6") (pinfunction "INT1_6") (pintype "passive"))
      (node (ref "P1") (pin "38") (pinfunction "38_38") (pintype "passive"))
      (node (ref "SW2") (pin "8") (pinfunction "8_8") (pintype "passive"))
    )
    (net (code "38") (name "/INT2") (class "Default")
      (node (ref "IC1") (pin "7") (pinfunction "INT2_7") (pintype "passive"))
      (node (ref "IC10") (pin "7") (pinfunction "INT2_7") (pintype "passive"))
      (node (ref "IC11") (pin "7") (pinfunction "INT2_7") (pintype "passive"))
      (node (ref "IC12") (pin "7") (pinfunction "INT2_7") (pintype "passive"))
      (node (ref "IC13") (pin "7") (pinfunction "INT2_7") (pintype "passive"))
      (node (ref "IC14") (pin "7") (pinfunction "INT2_7") (pintype "passive"))
      (node (ref "IC15") (pin "7") (pinfunction "INT2_7") (pintype "passive"))
      (node (ref "IC16") (pin "7") (pinfunction "INT2_7") (pintype "passive"))
      (node (ref "IC2") (pin "7") (pinfunction "INT2_7") (pintype "passive"))
      (node (ref "IC3") (pin "7") (pinfunction "INT2_7") (pintype "passive"))
      (node (ref "IC4") (pin "7") (pinfunction "INT2_7") (pintype "passive"))
      (node (ref "IC5") (pin "7") (pinfunction "INT2_7") (pintype "passive"))
      (node (ref "IC6") (pin "7") (pinfunction "INT2_7") (pintype "passive"))
      (node (ref "IC7") (pin "7") (pinfunction "INT2_7") (pintype "passive"))
      (node (ref "IC8") (pin "7") (pinfunction "INT2_7") (pintype "passive"))
      (node (ref "IC9") (pin "7") (pinfunction "INT2_7") (pintype "passive"))
      (node (ref "J1") (pin "5") (pinfunction "5_5") (pintype "passive"))
      (node (ref "P1") (pin "60") (pinfunction "60_60") (pintype "passive"))
    )
    (net (code "39") (name "/LFCLK") (class "Default")
      (node (ref "IC1") (pin "9") (pinfunction "LFCLK_9") (pintype "passive"))
      (node (ref "IC10") (pin "9") (pinfunction "LFCLK_9") (pintype "passive"))
      (node (ref "IC11") (pin "9") (pinfunction "LFCLK_9") (pintype "passive"))
      (node (ref "IC12") (pin "9") (pinfunction "LFCLK_9") (pintype "passive"))
      (node (ref "IC13") (pin "9") (pinfunction "LFCLK_9") (pintype "passive"))
      (node (ref "IC14") (pin "9") (pinfunction "LFCLK_9") (pintype "passive"))
      (node (ref "IC15") (pin "9") (pinfunction "LFCLK_9") (pintype "passive"))
      (node (ref "IC16") (pin "9") (pinfunction "LFCLK_9") (pintype "passive"))
      (node (ref "IC2") (pin "9") (pinfunction "LFCLK_9") (pintype "passive"))
      (node (ref "IC3") (pin "9") (pinfunction "LFCLK_9") (pintype "passive"))
      (node (ref "IC4") (pin "9") (pinfunction "LFCLK_9") (pintype "passive"))
      (node (ref "IC5") (pin "9") (pinfunction "LFCLK_9") (pintype "passive"))
      (node (ref "IC6") (pin "9") (pinfunction "LFCLK_9") (pintype "passive"))
      (node (ref "IC7") (pin "9") (pinfunction "LFCLK_9") (pintype "passive"))
      (node (ref "IC8") (pin "9") (pinfunction "LFCLK_9") (pintype "passive"))
      (node (ref "IC9") (pin "9") (pinfunction "LFCLK_9") (pintype "passive"))
      (node (ref "J1") (pin "4") (pinfunction "4_4") (pintype "passive"))
      (node (ref "P1") (pin "59") (pinfunction "59_59") (pintype "passive"))
    )
    (net (code "40") (name "/MISO") (class "Default")
      (node (ref "J1") (pin "8") (pinfunction "8_8") (pintype "passive"))
      (node (ref "SW5") (pin "10") (pinfunction "10_10") (pintype "passive"))
      (node (ref "SW5") (pin "11") (pinfunction "11_11") (pintype "passive"))
      (node (ref "SW5") (pin "12") (pinfunction "12_12") (pintype "passive"))
      (node (ref "SW5") (pin "13") (pinfunction "13_13") (pintype "passive"))
      (node (ref "SW5") (pin "14") (pinfunction "14_14") (pintype "passive"))
      (node (ref "SW5") (pin "15") (pinfunction "15_15") (pintype "passive"))
      (node (ref "SW5") (pin "16") (pinfunction "16_16") (pintype "passive"))
      (node (ref "SW5") (pin "9") (pinfunction "9_9") (pintype "passive"))
      (node (ref "SW6") (pin "10") (pinfunction "10_10") (pintype "passive"))
      (node (ref "SW6") (pin "11") (pinfunction "11_11") (pintype "passive"))
      (node (ref "SW6") (pin "12") (pinfunction "12_12") (pintype "passive"))
      (node (ref "SW6") (pin "13") (pinfunction "13_13") (pintype "passive"))
      (node (ref "SW6") (pin "14") (pinfunction "14_14") (pintype "passive"))
      (node (ref "SW6") (pin "15") (pinfunction "15_15") (pintype "passive"))
      (node (ref "SW6") (pin "16") (pinfunction "16_16") (pintype "passive"))
      (node (ref "SW6") (pin "9") (pinfunction "9_9") (pintype "passive"))
    )
    (net (code "41") (name "/MISO_1") (class "Default")
      (node (ref "IC1") (pin "4") (pinfunction "MISO_4") (pintype "passive"))
      (node (ref "P1") (pin "39") (pinfunction "39_39") (pintype "passive"))
      (node (ref "SW5") (pin "1") (pinfunction "1_1") (pintype "passive"))
    )
    (net (code "42") (name "/MISO_2") (class "Default")
      (node (ref "IC2") (pin "4") (pinfunction "MISO_4") (pintype "passive"))
      (node (ref "P1") (pin "40") (pinfunction "40_40") (pintype "passive"))
      (node (ref "SW5") (pin "2") (pinfunction "2_2") (pintype "passive"))
    )
    (net (code "43") (name "/MISO_3") (class "Default")
      (node (ref "IC3") (pin "4") (pinfunction "MISO_4") (pintype "passive"))
      (node (ref "P1") (pin "41") (pinfunction "41_41") (pintype "passive"))
      (node (ref "SW5") (pin "3") (pinfunction "3_3") (pintype "passive"))
    )
    (net (code "44") (name "/MISO_4") (class "Default")
      (node (ref "IC4") (pin "4") (pinfunction "MISO_4") (pintype "passive"))
      (node (ref "P1") (pin "42") (pinfunction "42_42") (pintype "passive"))
      (node (ref "SW5") (pin "4") (pinfunction "4_4") (pintype "passive"))
    )
    (net (code "45") (name "/MISO_5") (class "Default")
      (node (ref "IC5") (pin "4") (pinfunction "MISO_4") (pintype "passive"))
      (node (ref "P1") (pin "43") (pinfunction "43_43") (pintype "passive"))
      (node (ref "SW5") (pin "5") (pinfunction "5_5") (pintype "passive"))
    )
    (net (code "46") (name "/MISO_6") (class "Default")
      (node (ref "IC6") (pin "4") (pinfunction "MISO_4") (pintype "passive"))
      (node (ref "P1") (pin "44") (pinfunction "44_44") (pintype "passive"))
      (node (ref "SW5") (pin "6") (pinfunction "6_6") (pintype "passive"))
    )
    (net (code "47") (name "/MISO_7") (class "Default")
      (node (ref "IC7") (pin "4") (pinfunction "MISO_4") (pintype "passive"))
      (node (ref "P1") (pin "45") (pinfunction "45_45") (pintype "passive"))
      (node (ref "SW5") (pin "7") (pinfunction "7_7") (pintype "passive"))
    )
    (net (code "48") (name "/MISO_8") (class "Default")
      (node (ref "IC8") (pin "4") (pinfunction "MISO_4") (pintype "passive"))
      (node (ref "P1") (pin "46") (pinfunction "46_46") (pintype "passive"))
      (node (ref "SW5") (pin "8") (pinfunction "8_8") (pintype "passive"))
    )
    (net (code "49") (name "/MISO_9") (class "Default")
      (node (ref "IC9") (pin "4") (pinfunction "MISO_4") (pintype "passive"))
      (node (ref "P1") (pin "47") (pinfunction "47_47") (pintype "passive"))
      (node (ref "SW6") (pin "1") (pinfunction "1_1") (pintype "passive"))
    )
    (net (code "50") (name "/MISO_10") (class "Default")
      (node (ref "IC10") (pin "4") (pinfunction "MISO_4") (pintype "passive"))
      (node (ref "P1") (pin "48") (pinfunction "48_48") (pintype "passive"))
      (node (ref "SW6") (pin "2") (pinfunction "2_2") (pintype "passive"))
    )
    (net (code "51") (name "/MISO_11") (class "Default")
      (node (ref "IC11") (pin "4") (pinfunction "MISO_4") (pintype "passive"))
      (node (ref "P1") (pin "49") (pinfunction "49_49") (pintype "passive"))
      (node (ref "SW6") (pin "3") (pinfunction "3_3") (pintype "passive"))
    )
    (net (code "52") (name "/MISO_12") (class "Default")
      (node (ref "IC12") (pin "4") (pinfunction "MISO_4") (pintype "passive"))
      (node (ref "P1") (pin "50") (pinfunction "50_50") (pintype "passive"))
      (node (ref "SW6") (pin "4") (pinfunction "4_4") (pintype "passive"))
    )
    (net (code "53") (name "/MISO_13") (class "Default")
      (node (ref "IC13") (pin "4") (pinfunction "MISO_4") (pintype "passive"))
      (node (ref "P1") (pin "51") (pinfunction "51_51") (pintype "passive"))
      (node (ref "SW6") (pin "5") (pinfunction "5_5") (pintype "passive"))
    )
    (net (code "54") (name "/MISO_14") (class "Default")
      (node (ref "IC14") (pin "4") (pinfunction "MISO_4") (pintype "passive"))
      (node (ref "P1") (pin "52") (pinfunction "52_52") (pintype "passive"))
      (node (ref "SW6") (pin "6") (pinfunction "6_6") (pintype "passive"))
    )
    (net (code "55") (name "/MISO_15") (class "Default")
      (node (ref "IC15") (pin "4") (pinfunction "MISO_4") (pintype "passive"))
      (node (ref "P1") (pin "53") (pinfunction "53_53") (pintype "passive"))
      (node (ref "SW6") (pin "7") (pinfunction "7_7") (pintype "passive"))
    )
    (net (code "56") (name "/MISO_16") (class "Default")
      (node (ref "IC16") (pin "4") (pinfunction "MISO_4") (pintype "passive"))
      (node (ref "P1") (pin "54") (pinfunction "54_54") (pintype "passive"))
      (node (ref "SW6") (pin "8") (pinfunction "8_8") (pintype "passive"))
    )
    (net (code "57") (name "/MOSI") (class "Default")
      (node (ref "J1") (pin "9") (pinfunction "9_9") (pintype "passive"))
      (node (ref "SW8") (pin "5") (pinfunction "5_5") (pintype "passive"))
      (node (ref "SW8") (pin "6") (pinfunction "6_6") (pintype "passive"))
    )
    (net (code "58") (name "/MOSI_1") (class "Default")
      (node (ref "IC1") (pin "3") (pinfunction "MOSI_3") (pintype "passive"))
      (node (ref "IC2") (pin "3") (pinfunction "MOSI_3") (pintype "passive"))
      (node (ref "IC3") (pin "3") (pinfunction "MOSI_3") (pintype "passive"))
      (node (ref "IC4") (pin "3") (pinfunction "MOSI_3") (pintype "passive"))
      (node (ref "IC5") (pin "3") (pinfunction "MOSI_3") (pintype "passive"))
      (node (ref "IC6") (pin "3") (pinfunction "MOSI_3") (pintype "passive"))
      (node (ref "IC7") (pin "3") (pinfunction "MOSI_3") (pintype "passive"))
      (node (ref "IC8") (pin "3") (pinfunction "MOSI_3") (pintype "passive"))
      (node (ref "P1") (pin "5") (pinfunction "5_5") (pintype "passive"))
      (node (ref "SW8") (pin "3") (pinfunction "3_3") (pintype "passive"))
    )
    (net (code "59") (name "/MOSI_2") (class "Default")
      (node (ref "IC10") (pin "3") (pinfunction "MOSI_3") (pintype "passive"))
      (node (ref "IC11") (pin "3") (pinfunction "MOSI_3") (pintype "passive"))
      (node (ref "IC12") (pin "3") (pinfunction "MOSI_3") (pintype "passive"))
      (node (ref "IC13") (pin "3") (pinfunction "MOSI_3") (pintype "passive"))
      (node (ref "IC14") (pin "3") (pinfunction "MOSI_3") (pintype "passive"))
      (node (ref "IC15") (pin "3") (pinfunction "MOSI_3") (pintype "passive"))
      (node (ref "IC16") (pin "3") (pinfunction "MOSI_3") (pintype "passive"))
      (node (ref "IC9") (pin "3") (pinfunction "MOSI_3") (pintype "passive"))
      (node (ref "P1") (pin "6") (pinfunction "6_6") (pintype "passive"))
      (node (ref "SW8") (pin "4") (pinfunction "4_4") (pintype "passive"))
    )
    (net (code "60") (name "/MUTCLK") (class "Default")
      (node (ref "IC1") (pin "10") (pinfunction "MUTCLK_10") (pintype "passive"))
      (node (ref "IC10") (pin "10") (pinfunction "MUTCLK_10") (pintype "passive"))
      (node (ref "IC11") (pin "10") (pinfunction "MUTCLK_10") (pintype "passive"))
      (node (ref "IC12") (pin "10") (pinfunction "MUTCLK_10") (pintype "passive"))
      (node (ref "IC13") (pin "10") (pinfunction "MUTCLK_10") (pintype "passive"))
      (node (ref "IC14") (pin "10") (pinfunction "MUTCLK_10") (pintype "passive"))
      (node (ref "IC15") (pin "10") (pinfunction "MUTCLK_10") (pintype "passive"))
      (node (ref "IC16") (pin "10") (pinfunction "MUTCLK_10") (pintype "passive"))
      (node (ref "IC2") (pin "10") (pinfunction "MUTCLK_10") (pintype "passive"))
      (node (ref "IC3") (pin "10") (pinfunction "MUTCLK_10") (pintype "passive"))
      (node (ref "IC4") (pin "10") (pinfunction "MUTCLK_10") (pintype "passive"))
      (node (ref "IC5") (pin "10") (pinfunction "MUTCLK_10") (pintype "passive"))
      (node (ref "IC6") (pin "10") (pinfunction "MUTCLK_10") (pintype "passive"))
      (node (ref "IC7") (pin "10") (pinfunction "MUTCLK_10") (pintype "passive"))
      (node (ref "IC8") (pin "10") (pinfunction "MUTCLK_10") (pintype "passive"))
      (node (ref "IC9") (pin "10") (pinfunction "MUTCLK_10") (pintype "passive"))
      (node (ref "J1") (pin "3") (pinfunction "3_3") (pintype "passive"))
      (node (ref "P1") (pin "63") (pinfunction "63_63") (pintype "passive"))
    )
    (net (code "61") (name "/SCLK") (class "Default")
      (node (ref "J1") (pin "10") (pinfunction "10_10") (pintype "passive"))
      (node (ref "SW8") (pin "7") (pinfunction "7_7") (pintype "passive"))
      (node (ref "SW8") (pin "8") (pinfunction "8_8") (pintype "passive"))
    )
    (net (code "62") (name "/SCLK1") (class "Default")
      (node (ref "IC1") (pin "2") (pinfunction "SCLK_2") (pintype "passive"))
      (node (ref "IC2") (pin "2") (pinfunction "SCLK_2") (pintype "passive"))
      (node (ref "IC3") (pin "2") (pinfunction "SCLK_2") (pintype "passive"))
      (node (ref "IC4") (pin "2") (pinfunction "SCLK_2") (pintype "passive"))
      (node (ref "IC5") (pin "2") (pinfunction "SCLK_2") (pintype "passive"))
      (node (ref "IC6") (pin "2") (pinfunction "SCLK_2") (pintype "passive"))
      (node (ref "IC7") (pin "2") (pinfunction "SCLK_2") (pintype "passive"))
      (node (ref "IC8") (pin "2") (pinfunction "SCLK_2") (pintype "passive"))
      (node (ref "P1") (pin "1") (pinfunction "1_1") (pintype "passive"))
      (node (ref "SW8") (pin "1") (pinfunction "1_1") (pintype "passive"))
    )
    (net (code "63") (name "/SCLK2") (class "Default")
      (node (ref "IC10") (pin "2") (pinfunction "SCLK_2") (pintype "passive"))
      (node (ref "IC11") (pin "2") (pinfunction "SCLK_2") (pintype "passive"))
      (node (ref "IC12") (pin "2") (pinfunction "SCLK_2") (pintype "passive"))
      (node (ref "IC13") (pin "2") (pinfunction "SCLK_2") (pintype "passive"))
      (node (ref "IC14") (pin "2") (pinfunction "SCLK_2") (pintype "passive"))
      (node (ref "IC15") (pin "2") (pinfunction "SCLK_2") (pintype "passive"))
      (node (ref "IC16") (pin "2") (pinfunction "SCLK_2") (pintype "passive"))
      (node (ref "IC9") (pin "2") (pinfunction "SCLK_2") (pintype "passive"))
      (node (ref "P1") (pin "2") (pinfunction "2_2") (pintype "passive"))
      (node (ref "SW8") (pin "2") (pinfunction "2_2") (pintype "passive"))
    )
    (net (code "64") (name "/VDDIO") (class "Default")
      (node (ref "C17") (pin "2") (pinfunction "2_2") (pintype "passive"))
      (node (ref "C18") (pin "2") (pinfunction "2_2") (pintype "passive"))
      (node (ref "C19") (pin "2") (pinfunction "2_2") (pintype "passive"))
      (node (ref "C20") (pin "2") (pinfunction "2_2") (pintype "passive"))
      (node (ref "C21") (pin "2") (pinfunction "2_2") (pintype "passive"))
      (node (ref "C22") (pin "2") (pinfunction "2_2") (pintype "passive"))
      (node (ref "C23") (pin "2") (pinfunction "2_2") (pintype "passive"))
      (node (ref "C24") (pin "2") (pinfunction "2_2") (pintype "passive"))
      (node (ref "C25") (pin "2") (pinfunction "2_2") (pintype "passive"))
      (node (ref "C26") (pin "2") (pinfunction "2_2") (pintype "passive"))
      (node (ref "C27") (pin "2") (pinfunction "2_2") (pintype "passive"))
      (node (ref "C28") (pin "2") (pinfunction "2_2") (pintype "passive"))
      (node (ref "C29") (pin "2") (pinfunction "2_2") (pintype "passive"))
      (node (ref "C30") (pin "2") (pinfunction "2_2") (pintype "passive"))
      (node (ref "C31") (pin "2") (pinfunction "2_2") (pintype "passive"))
      (node (ref "C32") (pin "2") (pinfunction "2_2") (pintype "passive"))
      (node (ref "IC1") (pin "14") (pinfunction "VDDIO_14") (pintype "passive"))
      (node (ref "IC10") (pin "14") (pinfunction "VDDIO_14") (pintype "passive"))
      (node (ref "IC11") (pin "14") (pinfunction "VDDIO_14") (pintype "passive"))
      (node (ref "IC12") (pin "14") (pinfunction "VDDIO_14") (pintype "passive"))
      (node (ref "IC13") (pin "14") (pinfunction "VDDIO_14") (pintype "passive"))
      (node (ref "IC14") (pin "14") (pinfunction "VDDIO_14") (pintype "passive"))
      (node (ref "IC15") (pin "14") (pinfunction "VDDIO_14") (pintype "passive"))
      (node (ref "IC16") (pin "14") (pinfunction "VDDIO_14") (pintype "passive"))
      (node (ref "IC2") (pin "14") (pinfunction "VDDIO_14") (pintype "passive"))
      (node (ref "IC3") (pin "14") (pinfunction "VDDIO_14") (pintype "passive"))
      (node (ref "IC4") (pin "14") (pinfunction "VDDIO_14") (pintype "passive"))
      (node (ref "IC5") (pin "14") (pinfunction "VDDIO_14") (pintype "passive"))
      (node (ref "IC6") (pin "14") (pinfunction "VDDIO_14") (pintype "passive"))
      (node (ref "IC7") (pin "14") (pinfunction "VDDIO_14") (pintype "passive"))
      (node (ref "IC8") (pin "14") (pinfunction "VDDIO_14") (pintype "passive"))
      (node (ref "IC9") (pin "14") (pinfunction "VDDIO_14") (pintype "passive"))
      (node (ref "J1") (pin "12") (pinfunction "12_12") (pintype "passive"))
      (node (ref "P1") (pin "3") (pinfunction "3_3") (pintype "passive"))
      (node (ref "P1") (pin "4") (pinfunction "4_4") (pintype "passive"))
      (node (ref "P2") (pin "2") (pinfunction "2_2") (pintype "passive"))
    )
    (net (code "65") (name "GND") (class "Default")
      (node (ref "C1") (pin "1") (pinfunction "1_1") (pintype "passive"))
      (node (ref "C10") (pin "1") (pinfunction "1_1") (pintype "passive"))
      (node (ref "C11") (pin "1") (pinfunction "1_1") (pintype "passive"))
      (node (ref "C12") (pin "1") (pinfunction "1_1") (pintype "passive"))
      (node (ref "C13") (pin "1") (pinfunction "1_1") (pintype "passive"))
      (node (ref "C14") (pin "1") (pinfunction "1_1") (pintype "passive"))
      (node (ref "C15") (pin "1") (pinfunction "1_1") (pintype "passive"))
      (node (ref "C16") (pin "1") (pinfunction "1_1") (pintype "passive"))
      (node (ref "C17") (pin "1") (pinfunction "1_1") (pintype "passive"))
      (node (ref "C18") (pin "1") (pinfunction "1_1") (pintype "passive"))
      (node (ref "C19") (pin "1") (pinfunction "1_1") (pintype "passive"))
      (node (ref "C2") (pin "1") (pinfunction "1_1") (pintype "passive"))
      (node (ref "C20") (pin "1") (pinfunction "1_1") (pintype "passive"))
      (node (ref "C21") (pin "1") (pinfunction "1_1") (pintype "passive"))
      (node (ref "C22") (pin "1") (pinfunction "1_1") (pintype "passive"))
      (node (ref "C23") (pin "1") (pinfunction "1_1") (pintype "passive"))
      (node (ref "C24") (pin "1") (pinfunction "1_1") (pintype "passive"))
      (node (ref "C25") (pin "1") (pinfunction "1_1") (pintype "passive"))
      (node (ref "C26") (pin "1") (pinfunction "1_1") (pintype "passive"))
      (node (ref "C27") (pin "1") (pinfunction "1_1") (pintype "passive"))
      (node (ref "C28") (pin "1") (pinfunction "1_1") (pintype "passive"))
      (node (ref "C29") (pin "1") (pinfunction "1_1") (pintype "passive"))
      (node (ref "C3") (pin "1") (pinfunction "1_1") (pintype "passive"))
      (node (ref "C30") (pin "1") (pinfunction "1_1") (pintype "passive"))
      (node (ref "C31") (pin "1") (pinfunction "1_1") (pintype "passive"))
      (node (ref "C32") (pin "1") (pinfunction "1_1") (pintype "passive"))
      (node (ref "C33") (pin "2") (pinfunction "2_2") (pintype "passive"))
      (node (ref "C34") (pin "2") (pinfunction "2_2") (pintype "passive"))
      (node (ref "C35") (pin "2") (pinfunction "2_2") (pintype "passive"))
      (node (ref "C4") (pin "1") (pinfunction "1_1") (pintype "passive"))
      (node (ref "C5") (pin "1") (pinfunction "1_1") (pintype "passive"))
      (node (ref "C6") (pin "1") (pinfunction "1_1") (pintype "passive"))
      (node (ref "C7") (pin "1") (pinfunction "1_1") (pintype "passive"))
      (node (ref "C8") (pin "1") (pinfunction "1_1") (pintype "passive"))
      (node (ref "C9") (pin "1") (pinfunction "1_1") (pintype "passive"))
      (node (ref "IC1") (pin "1") (pinfunction "GND_1_1") (pintype "passive"))
      (node (ref "IC1") (pin "11") (pinfunction "GND_3_11") (pintype "passive"))
      (node (ref "IC1") (pin "8") (pinfunction "GND_2_8") (pintype "passive"))
      (node (ref "IC10") (pin "1") (pinfunction "GND_1_1") (pintype "passive"))
      (node (ref "IC10") (pin "11") (pinfunction "GND_3_11") (pintype "passive"))
      (node (ref "IC10") (pin "8") (pinfunction "GND_2_8") (pintype "passive"))
      (node (ref "IC11") (pin "1") (pinfunction "GND_1_1") (pintype "passive"))
      (node (ref "IC11") (pin "11") (pinfunction "GND_3_11") (pintype "passive"))
      (node (ref "IC11") (pin "8") (pinfunction "GND_2_8") (pintype "passive"))
      (node (ref "IC12") (pin "1") (pinfunction "GND_1_1") (pintype "passive"))
      (node (ref "IC12") (pin "11") (pinfunction "GND_3_11") (pintype "passive"))
      (node (ref "IC12") (pin "8") (pinfunction "GND_2_8") (pintype "passive"))
      (node (ref "IC13") (pin "1") (pinfunction "GND_1_1") (pintype "passive"))
      (node (ref "IC13") (pin "11") (pinfunction "GND_3_11") (pintype "passive"))
      (node (ref "IC13") (pin "8") (pinfunction "GND_2_8") (pintype "passive"))
      (node (ref "IC14") (pin "1") (pinfunction "GND_1_1") (pintype "passive"))
      (node (ref "IC14") (pin "11") (pinfunction "GND_3_11") (pintype "passive"))
      (node (ref "IC14") (pin "8") (pinfunction "GND_2_8") (pintype "passive"))
      (node (ref "IC15") (pin "1") (pinfunction "GND_1_1") (pintype "passive"))
      (node (ref "IC15") (pin "11") (pinfunction "GND_3_11") (pintype "passive"))
      (node (ref "IC15") (pin "8") (pinfunction "GND_2_8") (pintype "passive"))
      (node (ref "IC16") (pin "1") (pinfunction "GND_1_1") (pintype "passive"))
      (node (ref "IC16") (pin "11") (pinfunction "GND_3_11") (pintype "passive"))
      (node (ref "IC16") (pin "8") (pinfunction "GND_2_8") (pintype "passive"))
      (node (ref "IC2") (pin "1") (pinfunction "GND_1_1") (pintype "passive"))
      (node (ref "IC2") (pin "11") (pinfunction "GND_3_11") (pintype "passive"))
      (node (ref "IC2") (pin "8") (pinfunction "GND_2_8") (pintype "passive"))
      (node (ref "IC3") (pin "1") (pinfunction "GND_1_1") (pintype "passive"))
      (node (ref "IC3") (pin "11") (pinfunction "GND_3_11") (pintype "passive"))
      (node (ref "IC3") (pin "8") (pinfunction "GND_2_8") (pintype "passive"))
      (node (ref "IC4") (pin "1") (pinfunction "GND_1_1") (pintype "passive"))
      (node (ref "IC4") (pin "11") (pinfunction "GND_3_11") (pintype "passive"))
      (node (ref "IC4") (pin "8") (pinfunction "GND_2_8") (pintype "passive"))
      (node (ref "IC5") (pin "1") (pinfunction "GND_1_1") (pintype "passive"))
      (node (ref "IC5") (pin "11") (pinfunction "GND_3_11") (pintype "passive"))
      (node (ref "IC5") (pin "8") (pinfunction "GND_2_8") (pintype "passive"))
      (node (ref "IC6") (pin "1") (pinfunction "GND_1_1") (pintype "passive"))
      (node (ref "IC6") (pin "11") (pinfunction "GND_3_11") (pintype "passive"))
      (node (ref "IC6") (pin "8") (pinfunction "GND_2_8") (pintype "passive"))
      (node (ref "IC7") (pin "1") (pinfunction "GND_1_1") (pintype "passive"))
      (node (ref "IC7") (pin "11") (pinfunction "GND_3_11") (pintype "passive"))
      (node (ref "IC7") (pin "8") (pinfunction "GND_2_8") (pintype "passive"))
      (node (ref "IC8") (pin "1") (pinfunction "GND_1_1") (pintype "passive"))
      (node (ref "IC8") (pin "11") (pinfunction "GND_3_11") (pintype "passive"))
      (node (ref "IC8") (pin "8") (pinfunction "GND_2_8") (pintype "passive"))
      (node (ref "IC9") (pin "1") (pinfunction "GND_1_1") (pintype "passive"))
      (node (ref "IC9") (pin "11") (pinfunction "GND_3_11") (pintype "passive"))
      (node (ref "IC9") (pin "8") (pinfunction "GND_2_8") (pintype "passive"))
      (node (ref "J1") (pin "11") (pinfunction "11_11") (pintype "passive"))
      (node (ref "J1") (pin "13") (pinfunction "MNT_1_13") (pintype "passive"))
      (node (ref "J1") (pin "14") (pinfunction "MNT_2_14") (pintype "passive"))
      (node (ref "J1") (pin "2") (pinfunction "2_2") (pintype "passive"))
      (node (ref "P1") (pin "55") (pinfunction "55_55") (pintype "passive"))
      (node (ref "P1") (pin "57") (pinfunction "57_57") (pintype "passive"))
      (node (ref "P1") (pin "61") (pinfunction "61_61") (pintype "passive"))
      (node (ref "P1") (pin "62") (pinfunction "62_62") (pintype "passive"))
      (node (ref "P1") (pin "64") (pinfunction "64_64") (pintype "passive"))
      (node (ref "U1") (pin "3") (pinfunction "GND_3") (pintype "power_in"))
      (node (ref "U1") (pin "6") (pinfunction "GND_6") (pintype "power_in"))
    )
    (net (code "66") (name "Net-(U1-EN)") (class "Default")
      (node (ref "C33") (pin "1") (pinfunction "1_1") (pintype "passive"))
      (node (ref "P2") (pin "1") (pinfunction "1_1") (pintype "passive"))
      (node (ref "U1") (pin "1") (pinfunction "IN_1") (pintype "power_in"))
      (node (ref "U1") (pin "5") (pinfunction "EN_5") (pintype "input"))
    )
    (net (code "67") (name "Net-(U1-NR)") (class "Default")
      (node (ref "C35") (pin "1") (pinfunction "1_1") (pintype "passive"))
      (node (ref "U1") (pin "4") (pinfunction "NR_4") (pintype "passive"))
    )
  )
)
